# LA-3A.net
KiCad netlist of a schematic drawn in EAGLE
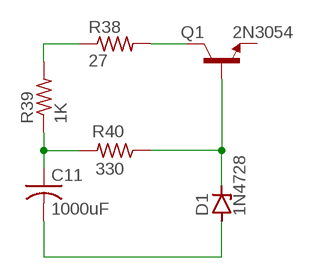
[diagram p0: schematic, sheet 1]

(export (version "E")
  (design (tool "Eeschema 10.0.6"))
  (components
    (comp (ref "C11")
      (value "1000uF")
      (footprint "eagle-import:C025-024X044")
      (libsource (lib "eagle-import") (part "C-US025-024X044"))
    )
    (comp (ref "D1")
      (value "1N4728")
      (footprint "eagle-import:DO41Z10")
      (libsource (lib "eagle-import") (part "1N4728"))
    )
    (comp (ref "Q1")
      (value "2N3054")
      (footprint "eagle-import:TO66")
      (libsource (lib "eagle-import") (part "2N3054"))
    )
    (comp (ref "R38")
      (value "27")
      (footprint "eagle-import:0204_7")
      (fields (field (name "POPULARITY") "27"))
      (libsource (lib "eagle-import") (part "R-US_0204/7"))
    )
    (comp (ref "R39")
      (value "1K")
      (footprint "eagle-import:0204_7")
      (libsource (lib "eagle-import") (part "R-US_0204/7"))
    )
    (comp (ref "R40")
      (value "330")
      (footprint "eagle-import:0204_7")
      (libsource (lib "eagle-import") (part "R-US_0204/7"))
    )
  )
  (nets
    (net (code "1") (name "Net-(C11-Pad1)") (class "Default")
      (node (ref "C11") (pin "1") (pinfunction "1_1") (pintype "passive"))
      (node (ref "R39") (pin "1") (pinfunction "1_1") (pintype "passive"))
      (node (ref "R40") (pin "2") (pinfunction "2_2") (pintype "passive"))
    )
    (net (code "2") (name "Net-(C11-Pad2)") (class "Default")
      (node (ref "C11") (pin "2") (pinfunction "2_2") (pintype "passive"))
      (node (ref "D1") (pin "A") (pinfunction "A_A") (pintype "passive"))
    )
    (net (code "3") (name "Net-(Q1-B)") (class "Default")
      (node (ref "D1") (pin "C") (pinfunction "C_C") (pintype "passive"))
      (node (ref "Q1") (pin "2") (pinfunction "B_2") (pintype "passive"))
      (node (ref "R40") (pin "1") (pinfunction "1_1") (pintype "passive"))
    )
    (net (code "4") (name "Net-(Q1-C-Pad3)") (class "Default")
      (node (ref "Q1") (pin "3") (pinfunction "C_3") (pintype "passive"))
      (node (ref "Q1") (pin "TO66") (pinfunction "C_TO66") (pintype "passive"))
      (node (ref "R38") (pin "2") (pinfunction "2_2") (pintype "passive"))
    )
    (net (code "5") (name "Net-(R38-Pad1)") (class "Default")
      (node (ref "R38") (pin "1") (pinfunction "1_1") (pintype "passive"))
      (node (ref "R39") (pin "2") (pinfunction "2_2") (pintype "passive"))
    )
    (net (code "6") (name "unconnected-(Q1-E-Pad1)") (class "Default")
      (node (ref "Q1") (pin "1") (pinfunction "E_1") (pintype "passive"))
    )
  )
)
